# HDMI_To_MIPI_PHY.net
KiCad netlist of a schematic drawn in Altium Designer
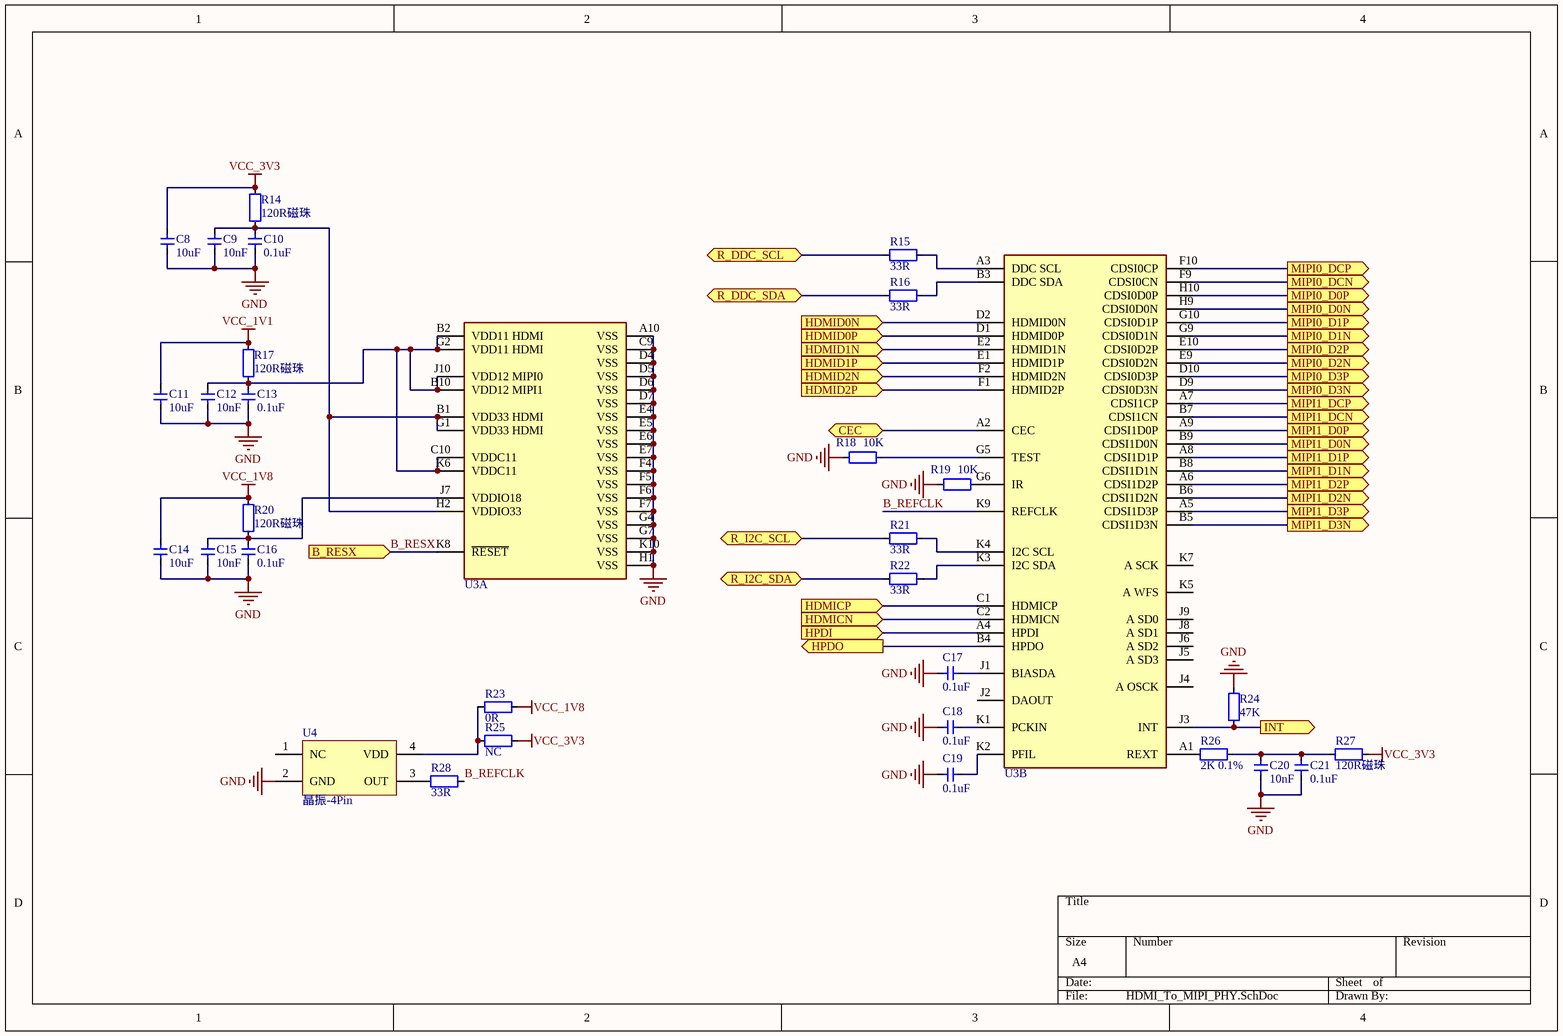
[diagram p0: HDMI_To_MIPI_PHY.SchDoc]

(export (version "E")
  (design (tool "Eeschema 10.0.6"))
  (components
    (comp (ref "C8")
      (value "10uF")
      (footprint "CAP_0402")
      (description "Capacitor")
      (libsource (lib "MyPcbLib") (part "电容-0402"))
    )
    (comp (ref "C9")
      (value "10nF")
      (footprint "CAP_0402")
      (description "Capacitor")
      (libsource (lib "MyPcbLib") (part "电容-0402"))
    )
    (comp (ref "C10")
      (value "0.1uF")
      (footprint "CAP_0402")
      (description "Capacitor")
      (libsource (lib "MyPcbLib") (part "电容-0402"))
    )
    (comp (ref "C11")
      (value "10uF")
      (footprint "CAP_0402")
      (description "Capacitor")
      (libsource (lib "MyPcbLib") (part "电容-0402"))
    )
    (comp (ref "C12")
      (value "10nF")
      (footprint "CAP_0402")
      (description "Capacitor")
      (libsource (lib "MyPcbLib") (part "电容-0402"))
    )
    (comp (ref "C13")
      (value "0.1uF")
      (footprint "CAP_0402")
      (description "Capacitor")
      (libsource (lib "MyPcbLib") (part "电容-0402"))
    )
    (comp (ref "C14")
      (value "10uF")
      (footprint "CAP_0402")
      (description "Capacitor")
      (libsource (lib "MyPcbLib") (part "电容-0402"))
    )
    (comp (ref "C15")
      (value "10nF")
      (footprint "CAP_0402")
      (description "Capacitor")
      (libsource (lib "MyPcbLib") (part "电容-0402"))
    )
    (comp (ref "C16")
      (value "0.1uF")
      (footprint "CAP_0402")
      (description "Capacitor")
      (libsource (lib "MyPcbLib") (part "电容-0402"))
    )
    (comp (ref "C17")
      (value "0.1uF")
      (footprint "CAP_0402")
      (description "Capacitor")
      (libsource (lib "MyPcbLib") (part "电容-0402"))
    )
    (comp (ref "C18")
      (value "0.1uF")
      (footprint "CAP_0402")
      (description "Capacitor")
      (libsource (lib "MyPcbLib") (part "电容-0402"))
    )
    (comp (ref "C19")
      (value "0.1uF")
      (footprint "CAP_0402")
      (description "Capacitor")
      (libsource (lib "MyPcbLib") (part "电容-0402"))
    )
    (comp (ref "C20")
      (value "10nF")
      (footprint "CAP_0402")
      (description "Capacitor")
      (libsource (lib "MyPcbLib") (part "电容-0402"))
    )
    (comp (ref "C21")
      (value "0.1uF")
      (footprint "CAP_0402")
      (description "Capacitor")
      (libsource (lib "MyPcbLib") (part "电容-0402"))
    )
    (comp (ref "R14")
      (value "120R磁珠")
      (footprint "0603_RES")
      (description "Resistor")
      (libsource (lib "MyPcbLib") (part "电阻-0805"))
    )
    (comp (ref "R15")
      (value "33R")
      (footprint "RES_0402")
      (description "Resistor")
      (libsource (lib "MyPcbLib") (part "电阻-0402"))
    )
    (comp (ref "R16")
      (value "33R")
      (footprint "RES_0402")
      (description "Resistor")
      (libsource (lib "MyPcbLib") (part "电阻-0402"))
    )
    (comp (ref "R17")
      (value "120R磁珠")
      (footprint "0603_RES")
      (description "Resistor")
      (libsource (lib "MyPcbLib") (part "电阻-0805"))
    )
    (comp (ref "R18")
      (value "10K")
      (footprint "RES_0402")
      (description "Resistor")
      (libsource (lib "MyPcbLib") (part "电阻-0402"))
    )
    (comp (ref "R19")
      (value "10K")
      (footprint "RES_0402")
      (description "Resistor")
      (libsource (lib "MyPcbLib") (part "电阻-0402"))
    )
    (comp (ref "R20")
      (value "120R磁珠")
      (footprint "0603_RES")
      (description "Resistor")
      (libsource (lib "MyPcbLib") (part "电阻-0805"))
    )
    (comp (ref "R21")
      (value "33R")
      (footprint "RES_0402")
      (description "Resistor")
      (libsource (lib "MyPcbLib") (part "电阻-0402"))
    )
    (comp (ref "R22")
      (value "33R")
      (footprint "RES_0402")
      (description "Resistor")
      (libsource (lib "MyPcbLib") (part "电阻-0402"))
    )
    (comp (ref "R23")
      (value "0R")
      (footprint "RES_0402")
      (description "Resistor")
      (libsource (lib "MyPcbLib") (part "电阻-0402"))
    )
    (comp (ref "R24")
      (value "47K")
      (footprint "RES_0402")
      (description "Resistor")
      (libsource (lib "") (part "电阻-0402_1"))
    )
    (comp (ref "R25")
      (value "NC")
      (footprint "RES_0402")
      (description "Resistor")
      (libsource (lib "MyPcbLib") (part "电阻-0402"))
    )
    (comp (ref "R26")
      (value "2K 0.1%")
      (footprint "RES_0402")
      (description "Resistor")
      (libsource (lib "MyPcbLib") (part "电阻-0402"))
    )
    (comp (ref "R27")
      (value "120R磁珠")
      (footprint "0603_RES")
      (description "Resistor")
      (libsource (lib "") (part "电阻-0805_1"))
    )
    (comp (ref "R28")
      (value "33R")
      (footprint "RES_0402")
      (description "Resistor")
      (libsource (lib "MyPcbLib") (part "电阻-0402"))
    )
    (comp (ref "U3")
      (value "TC358870XBG")
      (footprint "VFBGA-80")
      (libsource (lib "mLib") (part "TC358870XBG"))
    )
    (comp (ref "U4")
      (value "晶振-4Pin")
      (footprint "晶振2520")
      (description "5032 有源")
      (libsource (lib "mLib") (part "晶振-4Pin"))
    )
  )
  (nets
    (net (code "1") (name "/B_REFCLK") (class "Default")
      (node (ref "R28") (pin "2") (pinfunction "2_2") (pintype "passive"))
      (node (ref "U3") (pin "K9") (pinfunction "REFCLK_K9") (pintype "passive"))
    )
    (net (code "2") (name "/B_RESX") (class "Default")
      (node (ref "U3") (pin "K8") (pinfunction "~{RESET}_K8") (pintype "passive"))
    )
    (net (code "3") (name "/CEC") (class "Default")
      (node (ref "U3") (pin "A2") (pinfunction "CEC_A2") (pintype "passive"))
    )
    (net (code "4") (name "/HDMICN") (class "Default")
      (node (ref "U3") (pin "C2") (pinfunction "HDMICN_C2") (pintype "passive"))
    )
    (net (code "5") (name "/HDMICP") (class "Default")
      (node (ref "U3") (pin "C1") (pinfunction "HDMICP_C1") (pintype "passive"))
    )
    (net (code "6") (name "/HDMID0N") (class "Default")
      (node (ref "U3") (pin "D2") (pinfunction "HDMID0N_D2") (pintype "passive"))
    )
    (net (code "7") (name "/HDMID0P") (class "Default")
      (node (ref "U3") (pin "D1") (pinfunction "HDMID0P_D1") (pintype "passive"))
    )
    (net (code "8") (name "/HDMID1N") (class "Default")
      (node (ref "U3") (pin "E2") (pinfunction "HDMID1N_E2") (pintype "passive"))
    )
    (net (code "9") (name "/HDMID1P") (class "Default")
      (node (ref "U3") (pin "E1") (pinfunction "HDMID1P_E1") (pintype "passive"))
    )
    (net (code "10") (name "/HDMID2N") (class "Default")
      (node (ref "U3") (pin "F2") (pinfunction "HDMID2N_F2") (pintype "passive"))
    )
    (net (code "11") (name "/HDMID2P") (class "Default")
      (node (ref "U3") (pin "F1") (pinfunction "HDMID2P_F1") (pintype "passive"))
    )
    (net (code "12") (name "/HPDI") (class "Default")
      (node (ref "U3") (pin "A4") (pinfunction "HPDI_A4") (pintype "passive"))
    )
    (net (code "13") (name "/HPDO") (class "Default")
      (node (ref "U3") (pin "B4") (pinfunction "HPDO_B4") (pintype "passive"))
    )
    (net (code "14") (name "/INT") (class "Default")
      (node (ref "R24") (pin "1") (pinfunction "1_1") (pintype "passive"))
      (node (ref "U3") (pin "J3") (pinfunction "INT_J3") (pintype "passive"))
    )
    (net (code "15") (name "/MIPI0_D0N") (class "Default")
      (node (ref "U3") (pin "H9") (pinfunction "CDSI0D0N_H9") (pintype "passive"))
    )
    (net (code "16") (name "/MIPI0_D0P") (class "Default")
      (node (ref "U3") (pin "H10") (pinfunction "CDSI0D0P_H10") (pintype "passive"))
    )
    (net (code "17") (name "/MIPI0_D1N") (class "Default")
      (node (ref "U3") (pin "G9") (pinfunction "CDSI0D1N_G9") (pintype "passive"))
    )
    (net (code "18") (name "/MIPI0_D1P") (class "Default")
      (node (ref "U3") (pin "G10") (pinfunction "CDSI0D1P_G10") (pintype "passive"))
    )
    (net (code "19") (name "/MIPI0_D2N") (class "Default")
      (node (ref "U3") (pin "E9") (pinfunction "CDSI0D2N_E9") (pintype "passive"))
    )
    (net (code "20") (name "/MIPI0_D2P") (class "Default")
      (node (ref "U3") (pin "E10") (pinfunction "CDSI0D2P_E10") (pintype "passive"))
    )
    (net (code "21") (name "/MIPI0_D3N") (class "Default")
      (node (ref "U3") (pin "D9") (pinfunction "CDSI0D3N_D9") (pintype "passive"))
    )
    (net (code "22") (name "/MIPI0_D3P") (class "Default")
      (node (ref "U3") (pin "D10") (pinfunction "CDSI0D3P_D10") (pintype "passive"))
    )
    (net (code "23") (name "/MIPI0_DCN") (class "Default")
      (node (ref "U3") (pin "F9") (pinfunction "CDSI0CN_F9") (pintype "passive"))
    )
    (net (code "24") (name "/MIPI0_DCP") (class "Default")
      (node (ref "U3") (pin "F10") (pinfunction "CDSI0CP_F10") (pintype "passive"))
    )
    (net (code "25") (name "/MIPI1_D0N") (class "Default")
      (node (ref "U3") (pin "B9") (pinfunction "CDSI1D0N_B9") (pintype "passive"))
    )
    (net (code "26") (name "/MIPI1_D0P") (class "Default")
      (node (ref "U3") (pin "A9") (pinfunction "CDSI1D0P_A9") (pintype "passive"))
    )
    (net (code "27") (name "/MIPI1_D1N") (class "Default")
      (node (ref "U3") (pin "B8") (pinfunction "CDSI1D1N_B8") (pintype "passive"))
    )
    (net (code "28") (name "/MIPI1_D1P") (class "Default")
      (node (ref "U3") (pin "A8") (pinfunction "CDSI1D1P_A8") (pintype "passive"))
    )
    (net (code "29") (name "/MIPI1_D2N") (class "Default")
      (node (ref "U3") (pin "B6") (pinfunction "CDSI1D2N_B6") (pintype "passive"))
    )
    (net (code "30") (name "/MIPI1_D2P") (class "Default")
      (node (ref "U3") (pin "A6") (pinfunction "CDSI1D2P_A6") (pintype "passive"))
    )
    (net (code "31") (name "/MIPI1_D3N") (class "Default")
      (node (ref "U3") (pin "B5") (pinfunction "CDSI1D3N_B5") (pintype "passive"))
    )
    (net (code "32") (name "/MIPI1_D3P") (class "Default")
      (node (ref "U3") (pin "A5") (pinfunction "CDSI1D3P_A5") (pintype "passive"))
    )
    (net (code "33") (name "/MIPI1_DCN") (class "Default")
      (node (ref "U3") (pin "B7") (pinfunction "CDSI1CN_B7") (pintype "passive"))
    )
    (net (code "34") (name "/MIPI1_DCP") (class "Default")
      (node (ref "U3") (pin "A7") (pinfunction "CDSI1CP_A7") (pintype "passive"))
    )
    (net (code "35") (name "/R_DDC_SCL") (class "Default")
      (node (ref "R15") (pin "1") (pinfunction "1_1") (pintype "passive"))
    )
    (net (code "36") (name "/R_DDC_SDA") (class "Default")
      (node (ref "R16") (pin "1") (pinfunction "1_1") (pintype "passive"))
    )
    (net (code "37") (name "/R_I2C_SCL") (class "Default")
      (node (ref "R21") (pin "1") (pinfunction "1_1") (pintype "passive"))
    )
    (net (code "38") (name "/R_I2C_SDA") (class "Default")
      (node (ref "R22") (pin "1") (pinfunction "1_1") (pintype "passive"))
    )
    (net (code "39") (name "GND") (class "Default")
      (node (ref "C10") (pin "1") (pinfunction "1_1") (pintype "passive"))
      (node (ref "C11") (pin "1") (pinfunction "1_1") (pintype "passive"))
      (node (ref "C12") (pin "1") (pinfunction "1_1") (pintype "passive"))
      (node (ref "C13") (pin "1") (pinfunction "1_1") (pintype "passive"))
      (node (ref "C14") (pin "1") (pinfunction "1_1") (pintype "passive"))
      (node (ref "C15") (pin "1") (pinfunction "1_1") (pintype "passive"))
      (node (ref "C16") (pin "1") (pinfunction "1_1") (pintype "passive"))
      (node (ref "C17") (pin "2") (pinfunction "2_2") (pintype "passive"))
      (node (ref "C18") (pin "2") (pinfunction "2_2") (pintype "passive"))
      (node (ref "C19") (pin "2") (pinfunction "2_2") (pintype "passive"))
      (node (ref "C20") (pin "1") (pinfunction "1_1") (pintype "passive"))
      (node (ref "C21") (pin "1") (pinfunction "1_1") (pintype "passive"))
      (node (ref "C8") (pin "1") (pinfunction "1_1") (pintype "passive"))
      (node (ref "C9") (pin "1") (pinfunction "1_1") (pintype "passive"))
      (node (ref "R18") (pin "1") (pinfunction "1_1") (pintype "passive"))
      (node (ref "R19") (pin "1") (pinfunction "1_1") (pintype "passive"))
      (node (ref "R24") (pin "2") (pinfunction "2_2") (pintype "passive"))
      (node (ref "U3") (pin "A10") (pinfunction "VSS_A10") (pintype "passive"))
      (node (ref "U3") (pin "C9") (pinfunction "VSS_C9") (pintype "passive"))
      (node (ref "U3") (pin "D4") (pinfunction "VSS_D4") (pintype "passive"))
      (node (ref "U3") (pin "D5") (pinfunction "VSS_D5") (pintype "passive"))
      (node (ref "U3") (pin "D6") (pinfunction "VSS_D6") (pintype "passive"))
      (node (ref "U3") (pin "D7") (pinfunction "VSS_D7") (pintype "passive"))
      (node (ref "U3") (pin "E4") (pinfunction "VSS_E4") (pintype "passive"))
      (node (ref "U3") (pin "E5") (pinfunction "VSS_E5") (pintype "passive"))
      (node (ref "U3") (pin "E6") (pinfunction "VSS_E6") (pintype "passive"))
      (node (ref "U3") (pin "E7") (pinfunction "VSS_E7") (pintype "passive"))
      (node (ref "U3") (pin "F4") (pinfunction "VSS_F4") (pintype "passive"))
      (node (ref "U3") (pin "F5") (pinfunction "VSS_F5") (pintype "passive"))
      (node (ref "U3") (pin "F6") (pinfunction "VSS_F6") (pintype "passive"))
      (node (ref "U3") (pin "F7") (pinfunction "VSS_F7") (pintype "passive"))
      (node (ref "U3") (pin "G4") (pinfunction "VSS_G4") (pintype "passive"))
      (node (ref "U3") (pin "G7") (pinfunction "VSS_G7") (pintype "passive"))
      (node (ref "U3") (pin "H1") (pinfunction "VSS_H1") (pintype "passive"))
      (node (ref "U3") (pin "K10") (pinfunction "VSS_K10") (pintype "passive"))
      (node (ref "U4") (pin "2") (pinfunction "GND_2") (pintype "passive"))
    )
    (net (code "40") (name "Net-(C20-Pad2)") (class "Default")
      (node (ref "C20") (pin "2") (pinfunction "2_2") (pintype "passive"))
      (node (ref "C21") (pin "2") (pinfunction "2_2") (pintype "passive"))
      (node (ref "R26") (pin "2") (pinfunction "2_2") (pintype "passive"))
      (node (ref "R27") (pin "1") (pinfunction "1_1") (pintype "passive"))
    )
    (net (code "41") (name "Net-(U3A-VDD12_MIPI0)") (class "Default")
      (node (ref "C12") (pin "2") (pinfunction "2_2") (pintype "passive"))
      (node (ref "C13") (pin "2") (pinfunction "2_2") (pintype "passive"))
      (node (ref "R17") (pin "1") (pinfunction "1_1") (pintype "passive"))
      (node (ref "U3") (pin "B10") (pinfunction "VDD12_MIPI1_B10") (pintype "passive"))
      (node (ref "U3") (pin "B2") (pinfunction "VDD11_HDMI_B2") (pintype "passive"))
      (node (ref "U3") (pin "C10") (pinfunction "VDDC11_C10") (pintype "passive"))
      (node (ref "U3") (pin "G2") (pinfunction "VDD11_HDMI_G2") (pintype "passive"))
      (node (ref "U3") (pin "J10") (pinfunction "VDD12_MIPI0_J10") (pintype "passive"))
      (node (ref "U3") (pin "K6") (pinfunction "VDDC11_K6") (pintype "passive"))
    )
    (net (code "42") (name "Net-(U3A-VDDIO18)") (class "Default")
      (node (ref "C15") (pin "2") (pinfunction "2_2") (pintype "passive"))
      (node (ref "C16") (pin "2") (pinfunction "2_2") (pintype "passive"))
      (node (ref "R20") (pin "1") (pinfunction "1_1") (pintype "passive"))
      (node (ref "U3") (pin "J7") (pinfunction "VDDIO18_J7") (pintype "passive"))
    )
    (net (code "43") (name "Net-(U3A-VDDIO33)") (class "Default")
      (node (ref "C10") (pin "2") (pinfunction "2_2") (pintype "passive"))
      (node (ref "C9") (pin "2") (pinfunction "2_2") (pintype "passive"))
      (node (ref "R14") (pin "1") (pinfunction "1_1") (pintype "passive"))
      (node (ref "U3") (pin "B1") (pinfunction "VDD33_HDMI_B1") (pintype "passive"))
      (node (ref "U3") (pin "G1") (pinfunction "VDD33_HDMI_G1") (pintype "passive"))
      (node (ref "U3") (pin "H2") (pinfunction "VDDIO33_H2") (pintype "passive"))
    )
    (net (code "44") (name "Net-(U3B-BIASDA)") (class "Default")
      (node (ref "C17") (pin "1") (pinfunction "1_1") (pintype "passive"))
      (node (ref "U3") (pin "J1") (pinfunction "BIASDA_J1") (pintype "passive"))
    )
    (net (code "45") (name "Net-(U3B-DDC_SCL)") (class "Default")
      (node (ref "R15") (pin "2") (pinfunction "2_2") (pintype "passive"))
      (node (ref "U3") (pin "A3") (pinfunction "DDC_SCL_A3") (pintype "passive"))
    )
    (net (code "46") (name "Net-(U3B-DDC_SDA)") (class "Default")
      (node (ref "R16") (pin "2") (pinfunction "2_2") (pintype "passive"))
      (node (ref "U3") (pin "B3") (pinfunction "DDC_SDA_B3") (pintype "passive"))
    )
    (net (code "47") (name "Net-(U3B-I2C_SCL)") (class "Default")
      (node (ref "R21") (pin "2") (pinfunction "2_2") (pintype "passive"))
      (node (ref "U3") (pin "K4") (pinfunction "I2C_SCL_K4") (pintype "passive"))
    )
    (net (code "48") (name "Net-(U3B-I2C_SDA)") (class "Default")
      (node (ref "R22") (pin "2") (pinfunction "2_2") (pintype "passive"))
      (node (ref "U3") (pin "K3") (pinfunction "I2C_SDA_K3") (pintype "passive"))
    )
    (net (code "49") (name "Net-(U3B-IR)") (class "Default")
      (node (ref "R19") (pin "2") (pinfunction "2_2") (pintype "passive"))
      (node (ref "U3") (pin "G6") (pinfunction "IR_G6") (pintype "passive"))
    )
    (net (code "50") (name "Net-(U3B-PCKIN)") (class "Default")
      (node (ref "C18") (pin "1") (pinfunction "1_1") (pintype "passive"))
      (node (ref "U3") (pin "K1") (pinfunction "PCKIN_K1") (pintype "passive"))
    )
    (net (code "51") (name "Net-(U3B-PFIL)") (class "Default")
      (node (ref "C19") (pin "1") (pinfunction "1_1") (pintype "passive"))
      (node (ref "U3") (pin "K2") (pinfunction "PFIL_K2") (pintype "passive"))
    )
    (net (code "52") (name "Net-(U3B-REXT)") (class "Default")
      (node (ref "R26") (pin "1") (pinfunction "1_1") (pintype "passive"))
      (node (ref "U3") (pin "A1") (pinfunction "REXT_A1") (pintype "passive"))
    )
    (net (code "53") (name "Net-(U3B-TEST)") (class "Default")
      (node (ref "R18") (pin "2") (pinfunction "2_2") (pintype "passive"))
      (node (ref "U3") (pin "G5") (pinfunction "TEST_G5") (pintype "passive"))
    )
    (net (code "54") (name "Net-(U4-OUT)") (class "Default")
      (node (ref "R28") (pin "1") (pinfunction "1_1") (pintype "passive"))
      (node (ref "U4") (pin "3") (pinfunction "OUT_3") (pintype "passive"))
    )
    (net (code "55") (name "Net-(U4-VDD)") (class "Default")
      (node (ref "R23") (pin "1") (pinfunction "1_1") (pintype "passive"))
      (node (ref "R25") (pin "1") (pinfunction "1_1") (pintype "passive"))
      (node (ref "U4") (pin "4") (pinfunction "VDD_4") (pintype "passive"))
    )
    (net (code "56") (name "VCC_1V1") (class "Default")
      (node (ref "C11") (pin "2") (pinfunction "2_2") (pintype "passive"))
      (node (ref "R17") (pin "2") (pinfunction "2_2") (pintype "passive"))
    )
    (net (code "57") (name "VCC_1V8") (class "Default")
      (node (ref "C14") (pin "2") (pinfunction "2_2") (pintype "passive"))
      (node (ref "R20") (pin "2") (pinfunction "2_2") (pintype "passive"))
      (node (ref "R23") (pin "2") (pinfunction "2_2") (pintype "passive"))
    )
    (net (code "58") (name "VCC_3V3") (class "Default")
      (node (ref "C8") (pin "2") (pinfunction "2_2") (pintype "passive"))
      (node (ref "R14") (pin "2") (pinfunction "2_2") (pintype "passive"))
      (node (ref "R25") (pin "2") (pinfunction "2_2") (pintype "passive"))
      (node (ref "R27") (pin "2") (pinfunction "2_2") (pintype "passive"))
    )
    (net (code "59") (name "unconnected-(U3B-A_OSCK-PadJ4)") (class "Default")
      (node (ref "U3") (pin "J4") (pinfunction "A_OSCK_J4") (pintype "passive"))
    )
    (net (code "60") (name "unconnected-(U3B-A_SCK-PadK7)") (class "Default")
      (node (ref "U3") (pin "K7") (pinfunction "A_SCK_K7") (pintype "passive"))
    )
    (net (code "61") (name "unconnected-(U3B-A_SD0-PadJ9)") (class "Default")
      (node (ref "U3") (pin "J9") (pinfunction "A_SD0_J9") (pintype "passive"))
    )
    (net (code "62") (name "unconnected-(U3B-A_SD1-PadJ8)") (class "Default")
      (node (ref "U3") (pin "J8") (pinfunction "A_SD1_J8") (pintype "passive"))
    )
    (net (code "63") (name "unconnected-(U3B-A_SD2-PadJ6)") (class "Default")
      (node (ref "U3") (pin "J6") (pinfunction "A_SD2_J6") (pintype "passive"))
    )
    (net (code "64") (name "unconnected-(U3B-A_SD3-PadJ5)") (class "Default")
      (node (ref "U3") (pin "J5") (pinfunction "A_SD3_J5") (pintype "passive"))
    )
    (net (code "65") (name "unconnected-(U3B-A_WFS-PadK5)") (class "Default")
      (node (ref "U3") (pin "K5") (pinfunction "A_WFS_K5") (pintype "passive"))
    )
    (net (code "66") (name "unconnected-(U3B-DAOUT-PadJ2)") (class "Default")
      (node (ref "U3") (pin "J2") (pinfunction "DAOUT_J2") (pintype "passive"))
    )
    (net (code "67") (name "unconnected-(U4-NC-Pad1)") (class "Default")
      (node (ref "U4") (pin "1") (pinfunction "NC_1") (pintype "passive"))
    )
  )
)
